# Sheet_Con.net
KiCad netlist of a schematic drawn in Altium Designer
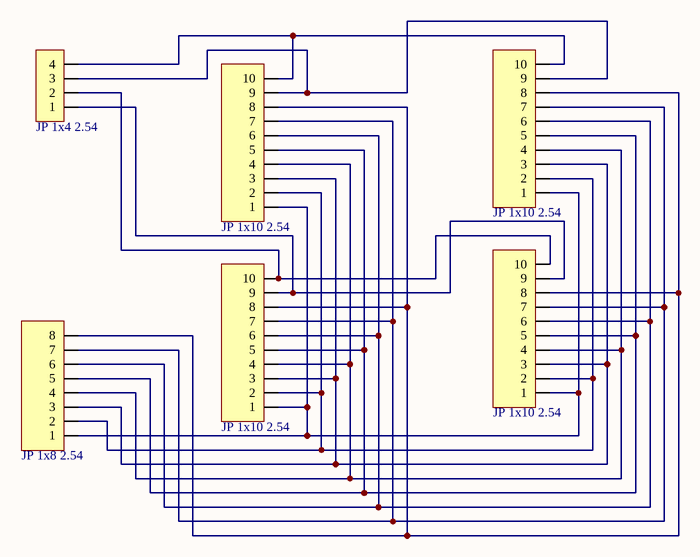
[diagram p0: Sheet_Con.SchDoc]

(export (version "E")
  (design (tool "Eeschema 10.0.6"))
  (components
    (comp (ref "7Seg11")
      (value "JP 1x10 2.54")
      (footprint "JP 1x10 DT")
      (description "Cắm")
      (libsource (lib "Altium_Lib_by_KhueNguyenCreator") (part "JP 1x10 2.54 Duc Thang"))
    )
    (comp (ref "7Seg12")
      (value "JP 1x10 2.54")
      (footprint "JP 1x10 DT")
      (description "Cắm")
      (libsource (lib "Altium_Lib_by_KhueNguyenCreator") (part "JP 1x10 2.54 Duc Thang"))
    )
    (comp (ref "7Seg21")
      (value "JP 1x10 2.54")
      (footprint "JP 1x10 DT")
      (description "Cắm")
      (libsource (lib "Altium_Lib_by_KhueNguyenCreator") (part "JP 1x10 2.54 Duc Thang"))
    )
    (comp (ref "7Seg22")
      (value "JP 1x10 2.54")
      (footprint "JP 1x10 DT")
      (description "Cắm")
      (libsource (lib "Altium_Lib_by_KhueNguyenCreator") (part "JP 1x10 2.54 Duc Thang"))
    )
    (comp (ref "Control7Seg")
      (value "JP 1x4 2.54")
      (footprint "JP 1x4 DT")
      (description "Cắm")
      (libsource (lib "Altium_Lib_by_KhueNguyenCreator") (part "JP 1x4 2.54 Duc Thang"))
    )
    (comp (ref "led_pin")
      (value "JP 1x8 2.54")
      (footprint "JP 1x8 DT")
      (description "Cắm")
      (libsource (lib "Altium_Lib_by_KhueNguyenCreator") (part "JP 1x8 2.54 Duc Thang"))
    )
  )
  (nets
    (net (code "1") (name "Net-(7Seg11-Pad1)") (class "Default")
      (node (ref "7Seg11") (pin "1") (pinfunction "1_1") (pintype "passive"))
      (node (ref "7Seg12") (pin "1") (pinfunction "1_1") (pintype "passive"))
      (node (ref "7Seg21") (pin "1") (pinfunction "1_1") (pintype "passive"))
      (node (ref "7Seg22") (pin "1") (pinfunction "1_1") (pintype "passive"))
      (node (ref "led_pin") (pin "1") (pinfunction "1_1") (pintype "passive"))
    )
    (net (code "2") (name "Net-(7Seg11-Pad2)") (class "Default")
      (node (ref "7Seg11") (pin "2") (pinfunction "2_2") (pintype "passive"))
      (node (ref "7Seg12") (pin "2") (pinfunction "2_2") (pintype "passive"))
      (node (ref "7Seg21") (pin "2") (pinfunction "2_2") (pintype "passive"))
      (node (ref "7Seg22") (pin "2") (pinfunction "2_2") (pintype "passive"))
      (node (ref "led_pin") (pin "2") (pinfunction "2_2") (pintype "passive"))
    )
    (net (code "3") (name "Net-(7Seg11-Pad3)") (class "Default")
      (node (ref "7Seg11") (pin "3") (pinfunction "3_3") (pintype "passive"))
      (node (ref "7Seg12") (pin "3") (pinfunction "3_3") (pintype "passive"))
      (node (ref "7Seg21") (pin "3") (pinfunction "3_3") (pintype "passive"))
      (node (ref "7Seg22") (pin "3") (pinfunction "3_3") (pintype "passive"))
      (node (ref "led_pin") (pin "3") (pinfunction "3_3") (pintype "passive"))
    )
    (net (code "4") (name "Net-(7Seg11-Pad4)") (class "Default")
      (node (ref "7Seg11") (pin "4") (pinfunction "4_4") (pintype "passive"))
      (node (ref "7Seg12") (pin "4") (pinfunction "4_4") (pintype "passive"))
      (node (ref "7Seg21") (pin "4") (pinfunction "4_4") (pintype "passive"))
      (node (ref "7Seg22") (pin "4") (pinfunction "4_4") (pintype "passive"))
      (node (ref "led_pin") (pin "4") (pinfunction "4_4") (pintype "passive"))
    )
    (net (code "5") (name "Net-(7Seg11-Pad5)") (class "Default")
      (node (ref "7Seg11") (pin "5") (pinfunction "5_5") (pintype "passive"))
      (node (ref "7Seg12") (pin "5") (pinfunction "5_5") (pintype "passive"))
      (node (ref "7Seg21") (pin "5") (pinfunction "5_5") (pintype "passive"))
      (node (ref "7Seg22") (pin "5") (pinfunction "5_5") (pintype "passive"))
      (node (ref "led_pin") (pin "5") (pinfunction "5_5") (pintype "passive"))
    )
    (net (code "6") (name "Net-(7Seg11-Pad6)") (class "Default")
      (node (ref "7Seg11") (pin "6") (pinfunction "6_6") (pintype "passive"))
      (node (ref "7Seg12") (pin "6") (pinfunction "6_6") (pintype "passive"))
      (node (ref "7Seg21") (pin "6") (pinfunction "6_6") (pintype "passive"))
      (node (ref "7Seg22") (pin "6") (pinfunction "6_6") (pintype "passive"))
      (node (ref "led_pin") (pin "6") (pinfunction "6_6") (pintype "passive"))
    )
    (net (code "7") (name "Net-(7Seg11-Pad7)") (class "Default")
      (node (ref "7Seg11") (pin "7") (pinfunction "7_7") (pintype "passive"))
      (node (ref "7Seg12") (pin "7") (pinfunction "7_7") (pintype "passive"))
      (node (ref "7Seg21") (pin "7") (pinfunction "7_7") (pintype "passive"))
      (node (ref "7Seg22") (pin "7") (pinfunction "7_7") (pintype "passive"))
      (node (ref "led_pin") (pin "7") (pinfunction "7_7") (pintype "passive"))
    )
    (net (code "8") (name "Net-(7Seg11-Pad8)") (class "Default")
      (node (ref "7Seg11") (pin "8") (pinfunction "8_8") (pintype "passive"))
      (node (ref "7Seg12") (pin "8") (pinfunction "8_8") (pintype "passive"))
      (node (ref "7Seg21") (pin "8") (pinfunction "8_8") (pintype "passive"))
      (node (ref "7Seg22") (pin "8") (pinfunction "8_8") (pintype "passive"))
      (node (ref "led_pin") (pin "8") (pinfunction "8_8") (pintype "passive"))
    )
    (net (code "9") (name "Net-(7Seg11-Pad9)") (class "Default")
      (node (ref "7Seg11") (pin "9") (pinfunction "9_9") (pintype "passive"))
      (node (ref "7Seg12") (pin "9") (pinfunction "9_9") (pintype "passive"))
      (node (ref "Control7Seg") (pin "1") (pinfunction "1_1") (pintype "passive"))
    )
    (net (code "10") (name "Net-(7Seg11-Pad10)") (class "Default")
      (node (ref "7Seg11") (pin "10") (pinfunction "10_10") (pintype "passive"))
      (node (ref "7Seg12") (pin "10") (pinfunction "10_10") (pintype "passive"))
      (node (ref "Control7Seg") (pin "2") (pinfunction "2_2") (pintype "passive"))
    )
    (net (code "11") (name "Net-(7Seg21-Pad9)") (class "Default")
      (node (ref "7Seg21") (pin "9") (pinfunction "9_9") (pintype "passive"))
      (node (ref "7Seg22") (pin "9") (pinfunction "9_9") (pintype "passive"))
      (node (ref "Control7Seg") (pin "3") (pinfunction "3_3") (pintype "passive"))
    )
    (net (code "12") (name "Net-(7Seg21-Pad10)") (class "Default")
      (node (ref "7Seg21") (pin "10") (pinfunction "10_10") (pintype "passive"))
      (node (ref "7Seg22") (pin "10") (pinfunction "10_10") (pintype "passive"))
      (node (ref "Control7Seg") (pin "4") (pinfunction "4_4") (pintype "passive"))
    )
  )
)
